# ultrasonic.net
KiCad netlist of a schematic drawn in EAGLE
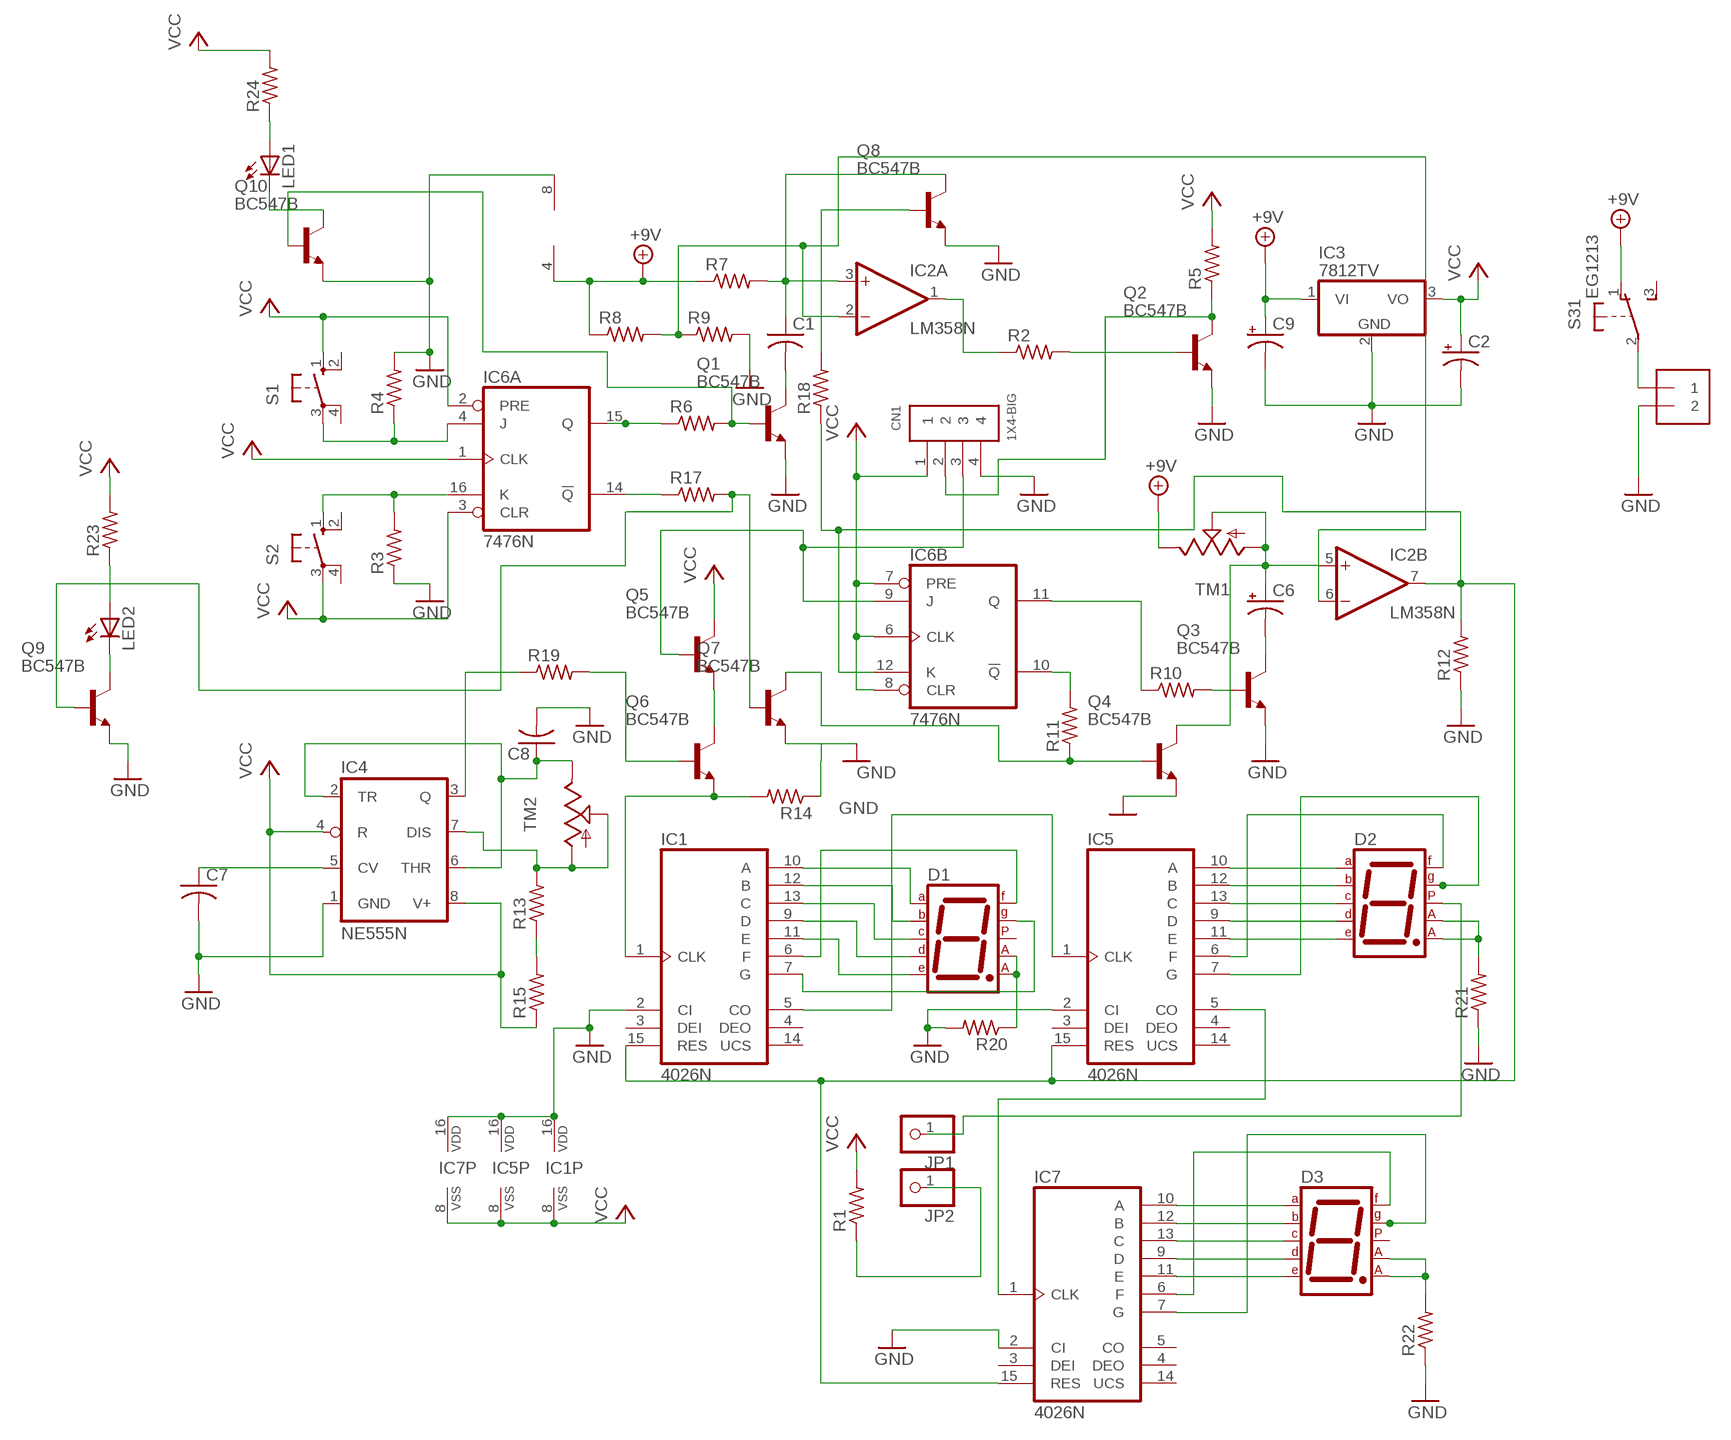
[diagram p0: schematic, sheet 1]

(export (version "E")
  (design (tool "Eeschema 10.0.6"))
  (components
    (comp (ref "C1")
      (value "C-US025-040X050")
      (footprint "eagle-import:C025-040X050")
      (libsource (lib "eagle-import") (part "C-US025-040X050"))
    )
    (comp (ref "C2")
      (value "CPOL-USE2-4")
      (footprint "eagle-import:E2-4")
      (libsource (lib "eagle-import") (part "CPOL-USE2-4"))
    )
    (comp (ref "C6")
      (value "CPOL-USE2.5-6")
      (footprint "eagle-import:E2,5-6")
      (libsource (lib "eagle-import") (part "CPOL-USE2.5-6"))
    )
    (comp (ref "C7")
      (value "C-US025-040X050")
      (footprint "eagle-import:C025-040X050")
      (libsource (lib "eagle-import") (part "C-US025-040X050"))
    )
    (comp (ref "C8")
      (value "C-US025-040X050")
      (footprint "eagle-import:C025-040X050")
      (libsource (lib "eagle-import") (part "C-US025-040X050"))
    )
    (comp (ref "C9")
      (value "CPOL-USE2.5-6")
      (footprint "eagle-import:E2,5-6")
      (libsource (lib "eagle-import") (part "CPOL-USE2.5-6"))
    )
    (comp (ref "CN1")
      (value "1X4-BIG")
      (footprint "eagle-import:1X04-BIG")
      (libsource (lib "eagle-import") (part "1X4-BIG"))
    )
    (comp (ref "D1")
      (value "7SEG-CA")
      (footprint "eagle-import:7SEG-13")
      (libsource (lib "eagle-import") (part "7SEG-CA"))
    )
    (comp (ref "D2")
      (value "7SEG-CA")
      (footprint "eagle-import:7SEG-13")
      (libsource (lib "eagle-import") (part "7SEG-CA"))
    )
    (comp (ref "D3")
      (value "7SEG-CA")
      (footprint "eagle-import:7SEG-13")
      (libsource (lib "eagle-import") (part "7SEG-CA"))
    )
    (comp (ref "IC1")
      (value "4026N")
      (footprint "eagle-import:DIL16")
      (libsource (lib "eagle-import") (part "4026N"))
    )
    (comp (ref "IC2")
      (value "LM358N")
      (footprint "eagle-import:DIL08")
      (libsource (lib "eagle-import") (part "LM358N"))
    )
    (comp (ref "IC3")
      (value "7812TV")
      (footprint "eagle-import:TO220V")
      (libsource (lib "eagle-import") (part "78TV12"))
    )
    (comp (ref "IC4")
      (value "NE555N")
      (footprint "eagle-import:DIL08-ROUND")
      (libsource (lib "eagle-import") (part "555NNE"))
    )
    (comp (ref "IC5")
      (value "4026N")
      (footprint "eagle-import:DIL16")
      (libsource (lib "eagle-import") (part "4026N"))
    )
    (comp (ref "IC6")
      (value "7476N")
      (footprint "eagle-import:DIL16")
      (libsource (lib "eagle-import") (part "7476N"))
    )
    (comp (ref "IC7")
      (value "4026N")
      (footprint "eagle-import:DIL16")
      (libsource (lib "eagle-import") (part "4026N"))
    )
    (comp (ref "J1")
      (value "1X2-3.5MM")
      (footprint "eagle-import:1X2-3.5MM")
      (libsource (lib "eagle-import") (part "1X2-3.5MM"))
    )
    (comp (ref "JP1")
      (value "PINHD-1X1")
      (footprint "eagle-import:1X01")
      (libsource (lib "eagle-import") (part "PINHD-1X1"))
    )
    (comp (ref "JP2")
      (value "PINHD-1X1")
      (footprint "eagle-import:1X01")
      (libsource (lib "eagle-import") (part "PINHD-1X1"))
    )
    (comp (ref "LED1")
      (value "LED5MM")
      (footprint "eagle-import:LED5MM")
      (libsource (lib "eagle-import") (part "LED5MM"))
    )
    (comp (ref "LED2")
      (value "LED5MM")
      (footprint "eagle-import:LED5MM")
      (libsource (lib "eagle-import") (part "LED5MM"))
    )
    (comp (ref "Q1")
      (value "BC547B")
      (footprint "eagle-import:TO92")
      (libsource (lib "eagle-import") (part "BC547B"))
    )
    (comp (ref "Q2")
      (value "BC547B")
      (footprint "eagle-import:TO92")
      (libsource (lib "eagle-import") (part "BC547B"))
    )
    (comp (ref "Q3")
      (value "BC547B")
      (footprint "eagle-import:TO92")
      (libsource (lib "eagle-import") (part "BC547B"))
    )
    (comp (ref "Q4")
      (value "BC547B")
      (footprint "eagle-import:TO92")
      (libsource (lib "eagle-import") (part "BC547B"))
    )
    (comp (ref "Q5")
      (value "BC547B")
      (footprint "eagle-import:TO92")
      (libsource (lib "eagle-import") (part "BC547B"))
    )
    (comp (ref "Q6")
      (value "BC547B")
      (footprint "eagle-import:TO92")
      (libsource (lib "eagle-import") (part "BC547B"))
    )
    (comp (ref "Q7")
      (value "BC547B")
      (footprint "eagle-import:TO92")
      (libsource (lib "eagle-import") (part "BC547B"))
    )
    (comp (ref "Q8")
      (value "BC547B")
      (footprint "eagle-import:TO92")
      (libsource (lib "eagle-import") (part "BC547B"))
    )
    (comp (ref "Q9")
      (value "BC547B")
      (footprint "eagle-import:TO92")
      (libsource (lib "eagle-import") (part "BC547B"))
    )
    (comp (ref "Q10")
      (value "BC547B")
      (footprint "eagle-import:TO92")
      (libsource (lib "eagle-import") (part "BC547B"))
    )
    (comp (ref "R1")
      (value "R-US_0204/7")
      (footprint "eagle-import:0204_7")
      (libsource (lib "eagle-import") (part "R-US_0204/7"))
    )
    (comp (ref "R2")
      (value "R-US_0204/7")
      (footprint "eagle-import:0204_7")
      (libsource (lib "eagle-import") (part "R-US_0204/7"))
    )
    (comp (ref "R3")
      (value "R-US_0204/7")
      (footprint "eagle-import:0204_7")
      (libsource (lib "eagle-import") (part "R-US_0204/7"))
    )
    (comp (ref "R4")
      (value "R-US_0204/7")
      (footprint "eagle-import:0204_7")
      (libsource (lib "eagle-import") (part "R-US_0204/7"))
    )
    (comp (ref "R5")
      (value "R-US_0204/7")
      (footprint "eagle-import:0204_7")
      (libsource (lib "eagle-import") (part "R-US_0204/7"))
    )
    (comp (ref "R6")
      (value "R-US_0204/7")
      (footprint "eagle-import:0204_7")
      (libsource (lib "eagle-import") (part "R-US_0204/7"))
    )
    (comp (ref "R7")
      (value "R-US_0204/7")
      (footprint "eagle-import:0204_7")
      (libsource (lib "eagle-import") (part "R-US_0204/7"))
    )
    (comp (ref "R8")
      (value "R-US_0204/7")
      (footprint "eagle-import:0204_7")
      (libsource (lib "eagle-import") (part "R-US_0204/7"))
    )
    (comp (ref "R9")
      (value "R-US_0204/7")
      (footprint "eagle-import:0204_7")
      (libsource (lib "eagle-import") (part "R-US_0204/7"))
    )
    (comp (ref "R10")
      (value "R-US_0204/7")
      (footprint "eagle-import:0204_7")
      (libsource (lib "eagle-import") (part "R-US_0204/7"))
    )
    (comp (ref "R11")
      (value "R-US_0204/7")
      (footprint "eagle-import:0204_7")
      (libsource (lib "eagle-import") (part "R-US_0204/7"))
    )
    (comp (ref "R12")
      (value "R-US_0204/7")
      (footprint "eagle-import:0204_7")
      (libsource (lib "eagle-import") (part "R-US_0204/7"))
    )
    (comp (ref "R13")
      (value "R-US_0204/7")
      (footprint "eagle-import:0204_7")
      (libsource (lib "eagle-import") (part "R-US_0204/7"))
    )
    (comp (ref "R14")
      (value "R-US_0204/7")
      (footprint "eagle-import:0204_7")
      (libsource (lib "eagle-import") (part "R-US_0204/7"))
    )
    (comp (ref "R15")
      (value "R-US_0204/7")
      (footprint "eagle-import:0204_7")
      (libsource (lib "eagle-import") (part "R-US_0204/7"))
    )
    (comp (ref "R17")
      (value "R-US_0204/7")
      (footprint "eagle-import:0204_7")
      (libsource (lib "eagle-import") (part "R-US_0204/7"))
    )
    (comp (ref "R18")
      (value "R-US_0204/7")
      (footprint "eagle-import:0204_7")
      (libsource (lib "eagle-import") (part "R-US_0204/7"))
    )
    (comp (ref "R19")
      (value "R-US_0204/7")
      (footprint "eagle-import:0204_7")
      (libsource (lib "eagle-import") (part "R-US_0204/7"))
    )
    (comp (ref "R20")
      (value "R-US_0204/7")
      (footprint "eagle-import:0204_7")
      (libsource (lib "eagle-import") (part "R-US_0204/7"))
    )
    (comp (ref "R21")
      (value "R-US_0204/7")
      (footprint "eagle-import:0204_7")
      (libsource (lib "eagle-import") (part "R-US_0204/7"))
    )
    (comp (ref "R22")
      (value "R-US_0204/7")
      (footprint "eagle-import:0204_7")
      (libsource (lib "eagle-import") (part "R-US_0204/7"))
    )
    (comp (ref "R23")
      (value "R-US_0204/7")
      (footprint "eagle-import:0204_7")
      (libsource (lib "eagle-import") (part "R-US_0204/7"))
    )
    (comp (ref "R24")
      (value "R-US_0204/7")
      (footprint "eagle-import:0204_7")
      (libsource (lib "eagle-import") (part "R-US_0204/7"))
    )
    (comp (ref "S1")
      (value "10-XX")
      (footprint "eagle-import:B3F-10XX")
      (fields (field (name "MPN") "B3F-1000"))
      (libsource (lib "eagle-import") (part "10-XX"))
    )
    (comp (ref "S2")
      (value "10-XX")
      (footprint "eagle-import:B3F-10XX")
      (fields (field (name "MPN") "B3F-1000"))
      (libsource (lib "eagle-import") (part "10-XX"))
    )
    (comp (ref "S3")
      (value "EG1213")
      (footprint "eagle-import:EG1213")
      (libsource (lib "eagle-import") (part "EG1213"))
    )
    (comp (ref "TM1")
      (value "TRIM")
      (footprint "eagle-import:6MM")
      (libsource (lib "eagle-import") (part "TRIM"))
    )
    (comp (ref "TM2")
      (value "TRIM")
      (footprint "eagle-import:6MM")
      (libsource (lib "eagle-import") (part "TRIM"))
    )
  )
  (nets
    (net (code "1") (name "+9V") (class "Default")
      (node (ref "C9") (pin "+") (pinfunction "+_+") (pintype "passive"))
      (node (ref "IC2") (pin "4") (pinfunction "V-_4") (pintype "power_in"))
      (node (ref "IC3") (pin "1") (pinfunction "VI_1") (pintype "input"))
      (node (ref "R7") (pin "1") (pinfunction "1_1") (pintype "passive"))
      (node (ref "R8") (pin "1") (pinfunction "1_1") (pintype "passive"))
      (node (ref "S3") (pin "1") (pinfunction "O_1") (pintype "passive"))
      (node (ref "TM1") (pin "E") (pinfunction "E_E") (pintype "passive"))
    )
    (net (code "2") (name "GND") (class "Default")
      (node (ref "C2") (pin "-") (pinfunction "-_-") (pintype "passive"))
      (node (ref "C7") (pin "2") (pinfunction "2_2") (pintype "passive"))
      (node (ref "C8") (pin "2") (pinfunction "2_2") (pintype "passive"))
      (node (ref "C9") (pin "-") (pinfunction "-_-") (pintype "passive"))
      (node (ref "CN1") (pin "4") (pinfunction "4_4") (pintype "bidirectional"))
      (node (ref "IC1") (pin "16") (pinfunction "VDD_16") (pintype "power_in"))
      (node (ref "IC1") (pin "2") (pinfunction "CI_2") (pintype "input"))
      (node (ref "IC2") (pin "8") (pinfunction "V+_8") (pintype "power_in"))
      (node (ref "IC3") (pin "2") (pinfunction "GND_2") (pintype "passive"))
      (node (ref "IC4") (pin "1") (pinfunction "GND_1") (pintype "power_in"))
      (node (ref "IC5") (pin "16") (pinfunction "VDD_16") (pintype "power_in"))
      (node (ref "IC5") (pin "2") (pinfunction "CI_2") (pintype "input"))
      (node (ref "IC7") (pin "16") (pinfunction "VDD_16") (pintype "power_in"))
      (node (ref "IC7") (pin "2") (pinfunction "CI_2") (pintype "input"))
      (node (ref "J1") (pin "2") (pinfunction "2_2") (pintype "passive"))
      (node (ref "Q1") (pin "1") (pinfunction "E_1") (pintype "passive"))
      (node (ref "Q10") (pin "1") (pinfunction "E_1") (pintype "passive"))
      (node (ref "Q2") (pin "1") (pinfunction "E_1") (pintype "passive"))
      (node (ref "Q3") (pin "1") (pinfunction "E_1") (pintype "passive"))
      (node (ref "Q4") (pin "1") (pinfunction "E_1") (pintype "passive"))
      (node (ref "Q7") (pin "1") (pinfunction "E_1") (pintype "passive"))
      (node (ref "Q8") (pin "1") (pinfunction "E_1") (pintype "passive"))
      (node (ref "Q9") (pin "1") (pinfunction "E_1") (pintype "passive"))
      (node (ref "R12") (pin "1") (pinfunction "1_1") (pintype "passive"))
      (node (ref "R14") (pin "1") (pinfunction "1_1") (pintype "passive"))
      (node (ref "R20") (pin "2") (pinfunction "2_2") (pintype "passive"))
      (node (ref "R21") (pin "1") (pinfunction "1_1") (pintype "passive"))
      (node (ref "R22") (pin "1") (pinfunction "1_1") (pintype "passive"))
      (node (ref "R3") (pin "1") (pinfunction "1_1") (pintype "passive"))
      (node (ref "R4") (pin "2") (pinfunction "2_2") (pintype "passive"))
      (node (ref "R9") (pin "2") (pinfunction "2_2") (pintype "passive"))
    )
    (net (code "3") (name "Net-(D1-A)") (class "Default")
      (node (ref "D1") (pin "7") (pinfunction "A_7") (pintype "passive"))
      (node (ref "IC1") (pin "10") (pinfunction "A_10") (pintype "output"))
    )
    (net (code "4") (name "Net-(D1-B)") (class "Default")
      (node (ref "D1") (pin "6") (pinfunction "B_6") (pintype "passive"))
      (node (ref "IC1") (pin "12") (pinfunction "B_12") (pintype "output"))
    )
    (net (code "5") (name "Net-(D1-C)") (class "Default")
      (node (ref "D1") (pin "4") (pinfunction "C_4") (pintype "passive"))
      (node (ref "IC1") (pin "13") (pinfunction "C_13") (pintype "output"))
    )
    (net (code "6") (name "Net-(D1-CA1)") (class "Default")
      (node (ref "D1") (pin "3") (pinfunction "CA1_3") (pintype "passive"))
      (node (ref "D1") (pin "8") (pinfunction "CA2_8") (pintype "passive"))
      (node (ref "R20") (pin "1") (pinfunction "1_1") (pintype "passive"))
    )
    (net (code "7") (name "Net-(D1-D)") (class "Default")
      (node (ref "D1") (pin "2") (pinfunction "D_2") (pintype "passive"))
      (node (ref "IC1") (pin "9") (pinfunction "D_9") (pintype "output"))
    )
    (net (code "8") (name "Net-(D1-E)") (class "Default")
      (node (ref "D1") (pin "1") (pinfunction "E_1") (pintype "passive"))
      (node (ref "IC1") (pin "11") (pinfunction "E_11") (pintype "output"))
    )
    (net (code "9") (name "Net-(D1-F)") (class "Default")
      (node (ref "D1") (pin "9") (pinfunction "F_9") (pintype "passive"))
      (node (ref "IC1") (pin "6") (pinfunction "F_6") (pintype "output"))
    )
    (net (code "10") (name "Net-(D1-G)") (class "Default")
      (node (ref "D1") (pin "10") (pinfunction "G_10") (pintype "passive"))
      (node (ref "IC1") (pin "7") (pinfunction "G_7") (pintype "output"))
    )
    (net (code "11") (name "Net-(D2-A)") (class "Default")
      (node (ref "D2") (pin "7") (pinfunction "A_7") (pintype "passive"))
      (node (ref "IC5") (pin "10") (pinfunction "A_10") (pintype "output"))
    )
    (net (code "12") (name "Net-(D2-B)") (class "Default")
      (node (ref "D2") (pin "6") (pinfunction "B_6") (pintype "passive"))
      (node (ref "IC5") (pin "12") (pinfunction "B_12") (pintype "output"))
    )
    (net (code "13") (name "Net-(D2-C)") (class "Default")
      (node (ref "D2") (pin "4") (pinfunction "C_4") (pintype "passive"))
      (node (ref "IC5") (pin "13") (pinfunction "C_13") (pintype "output"))
    )
    (net (code "14") (name "Net-(D2-CA1)") (class "Default")
      (node (ref "D2") (pin "3") (pinfunction "CA1_3") (pintype "passive"))
      (node (ref "D2") (pin "8") (pinfunction "CA2_8") (pintype "passive"))
      (node (ref "R21") (pin "2") (pinfunction "2_2") (pintype "passive"))
    )
    (net (code "15") (name "Net-(D2-D)") (class "Default")
      (node (ref "D2") (pin "2") (pinfunction "D_2") (pintype "passive"))
      (node (ref "IC5") (pin "9") (pinfunction "D_9") (pintype "output"))
    )
    (net (code "16") (name "Net-(D2-DP)") (class "Default")
      (node (ref "D2") (pin "5") (pinfunction "DP_5") (pintype "passive"))
      (node (ref "JP1") (pin "1") (pinfunction "1_1") (pintype "passive"))
    )
    (net (code "17") (name "Net-(D2-E)") (class "Default")
      (node (ref "D2") (pin "1") (pinfunction "E_1") (pintype "passive"))
      (node (ref "IC5") (pin "11") (pinfunction "E_11") (pintype "output"))
    )
    (net (code "18") (name "Net-(D2-F)") (class "Default")
      (node (ref "D2") (pin "9") (pinfunction "F_9") (pintype "passive"))
      (node (ref "IC5") (pin "6") (pinfunction "F_6") (pintype "output"))
    )
    (net (code "19") (name "Net-(D2-G)") (class "Default")
      (node (ref "D2") (pin "10") (pinfunction "G_10") (pintype "passive"))
      (node (ref "IC5") (pin "7") (pinfunction "G_7") (pintype "output"))
    )
    (net (code "20") (name "Net-(D3-A)") (class "Default")
      (node (ref "D3") (pin "7") (pinfunction "A_7") (pintype "passive"))
      (node (ref "IC7") (pin "10") (pinfunction "A_10") (pintype "output"))
    )
    (net (code "21") (name "Net-(D3-B)") (class "Default")
      (node (ref "D3") (pin "6") (pinfunction "B_6") (pintype "passive"))
      (node (ref "IC7") (pin "12") (pinfunction "B_12") (pintype "output"))
    )
    (net (code "22") (name "Net-(D3-C)") (class "Default")
      (node (ref "D3") (pin "4") (pinfunction "C_4") (pintype "passive"))
      (node (ref "IC7") (pin "13") (pinfunction "C_13") (pintype "output"))
    )
    (net (code "23") (name "Net-(D3-CA1)") (class "Default")
      (node (ref "D3") (pin "3") (pinfunction "CA1_3") (pintype "passive"))
      (node (ref "D3") (pin "8") (pinfunction "CA2_8") (pintype "passive"))
      (node (ref "R22") (pin "2") (pinfunction "2_2") (pintype "passive"))
    )
    (net (code "24") (name "Net-(D3-D)") (class "Default")
      (node (ref "D3") (pin "2") (pinfunction "D_2") (pintype "passive"))
      (node (ref "IC7") (pin "9") (pinfunction "D_9") (pintype "output"))
    )
    (net (code "25") (name "Net-(D3-E)") (class "Default")
      (node (ref "D3") (pin "1") (pinfunction "E_1") (pintype "passive"))
      (node (ref "IC7") (pin "11") (pinfunction "E_11") (pintype "output"))
    )
    (net (code "26") (name "Net-(D3-F)") (class "Default")
      (node (ref "D3") (pin "9") (pinfunction "F_9") (pintype "passive"))
      (node (ref "IC7") (pin "6") (pinfunction "F_6") (pintype "output"))
    )
    (net (code "27") (name "Net-(D3-G)") (class "Default")
      (node (ref "D3") (pin "10") (pinfunction "G_10") (pintype "passive"))
      (node (ref "IC7") (pin "7") (pinfunction "G_7") (pintype "output"))
    )
    (net (code "28") (name "Net-(IC1A-CLK)") (class "Default")
      (node (ref "IC1") (pin "1") (pinfunction "CLK_1") (pintype "input"))
      (node (ref "Q6") (pin "1") (pinfunction "E_1") (pintype "passive"))
      (node (ref "R14") (pin "2") (pinfunction "2_2") (pintype "passive"))
    )
    (net (code "29") (name "Net-(IC1A-CO)") (class "Default")
      (node (ref "IC1") (pin "5") (pinfunction "CO_5") (pintype "output"))
      (node (ref "IC5") (pin "1") (pinfunction "CLK_1") (pintype "input"))
    )
    (net (code "30") (name "Net-(IC1A-RES)") (class "Default")
      (node (ref "IC1") (pin "15") (pinfunction "RES_15") (pintype "input"))
      (node (ref "IC2") (pin "7") (pinfunction "OUT_7") (pintype "output"))
      (node (ref "IC5") (pin "15") (pinfunction "RES_15") (pintype "input"))
      (node (ref "IC6") (pin "12") (pinfunction "K_12") (pintype "input"))
      (node (ref "IC7") (pin "15") (pinfunction "RES_15") (pintype "input"))
      (node (ref "R12") (pin "2") (pinfunction "2_2") (pintype "passive"))
      (node (ref "R18") (pin "1") (pinfunction "1_1") (pintype "passive"))
    )
    (net (code "31") (name "Net-(IC2A-+IN)") (class "Default")
      (node (ref "C1") (pin "1") (pinfunction "1_1") (pintype "passive"))
      (node (ref "IC2") (pin "3") (pinfunction "+IN_3") (pintype "input"))
      (node (ref "Q8") (pin "3") (pinfunction "C_3") (pintype "passive"))
      (node (ref "R7") (pin "2") (pinfunction "2_2") (pintype "passive"))
    )
    (net (code "32") (name "Net-(IC2A--IN)") (class "Default")
      (node (ref "IC2") (pin "2") (pinfunction "-IN_2") (pintype "input"))
      (node (ref "IC2") (pin "6") (pinfunction "-IN_6") (pintype "input"))
      (node (ref "R8") (pin "2") (pinfunction "2_2") (pintype "passive"))
      (node (ref "R9") (pin "1") (pinfunction "1_1") (pintype "passive"))
    )
    (net (code "33") (name "Net-(IC2A-OUT)") (class "Default")
      (node (ref "IC2") (pin "1") (pinfunction "OUT_1") (pintype "output"))
      (node (ref "R2") (pin "1") (pinfunction "1_1") (pintype "passive"))
    )
    (net (code "34") (name "Net-(IC2B-+IN)") (class "Default")
      (node (ref "C6") (pin "+") (pinfunction "+_+") (pintype "passive"))
      (node (ref "IC2") (pin "5") (pinfunction "+IN_5") (pintype "input"))
      (node (ref "Q4") (pin "3") (pinfunction "C_3") (pintype "passive"))
      (node (ref "TM1") (pin "A") (pinfunction "A_A") (pintype "passive"))
      (node (ref "TM1") (pin "S") (pinfunction "S_S") (pintype "passive"))
    )
    (net (code "35") (name "Net-(IC4-CV)") (class "Default")
      (node (ref "C7") (pin "1") (pinfunction "1_1") (pintype "passive"))
      (node (ref "IC4") (pin "5") (pinfunction "CV_5") (pintype "input"))
    )
    (net (code "36") (name "Net-(IC4-DIS)") (class "Default")
      (node (ref "IC4") (pin "7") (pinfunction "DIS_7") (pintype "input"))
      (node (ref "R13") (pin "2") (pinfunction "2_2") (pintype "passive"))
      (node (ref "TM2") (pin "A") (pinfunction "A_A") (pintype "passive"))
      (node (ref "TM2") (pin "S") (pinfunction "S_S") (pintype "passive"))
    )
    (net (code "37") (name "Net-(IC4-Q)") (class "Default")
      (node (ref "IC4") (pin "3") (pinfunction "Q_3") (pintype "output"))
      (node (ref "R19") (pin "1") (pinfunction "1_1") (pintype "passive"))
    )
    (net (code "38") (name "Net-(IC4-THR)") (class "Default")
      (node (ref "C8") (pin "1") (pinfunction "1_1") (pintype "passive"))
      (node (ref "IC4") (pin "2") (pinfunction "TR_2") (pintype "input"))
      (node (ref "IC4") (pin "6") (pinfunction "THR_6") (pintype "input"))
      (node (ref "TM2") (pin "E") (pinfunction "E_E") (pintype "passive"))
    )
    (net (code "39") (name "Net-(IC5A-CO)") (class "Default")
      (node (ref "IC5") (pin "5") (pinfunction "CO_5") (pintype "output"))
      (node (ref "IC7") (pin "1") (pinfunction "CLK_1") (pintype "input"))
    )
    (net (code "40") (name "Net-(IC6A-J)") (class "Default")
      (node (ref "IC6") (pin "4") (pinfunction "J_4") (pintype "input"))
      (node (ref "R4") (pin "1") (pinfunction "1_1") (pintype "passive"))
      (node (ref "S1") (pin "3") (pinfunction "P_3") (pintype "passive"))
    )
    (net (code "41") (name "Net-(IC6A-K)") (class "Default")
      (node (ref "IC6") (pin "16") (pinfunction "K_16") (pintype "input"))
      (node (ref "R3") (pin "2") (pinfunction "2_2") (pintype "passive"))
      (node (ref "S2") (pin "1") (pinfunction "S_1") (pintype "passive"))
    )
    (net (code "42") (name "Net-(IC6A-Q)") (class "Default")
      (node (ref "IC6") (pin "15") (pinfunction "Q_15") (pintype "output"))
      (node (ref "R6") (pin "1") (pinfunction "1_1") (pintype "passive"))
    )
    (net (code "43") (name "Net-(IC6A-~{Q})") (class "Default")
      (node (ref "IC6") (pin "14") (pinfunction "~{Q}_14") (pintype "output"))
      (node (ref "R17") (pin "1") (pinfunction "1_1") (pintype "passive"))
    )
    (net (code "44") (name "Net-(IC6B-J)") (class "Default")
      (node (ref "CN1") (pin "3") (pinfunction "3_3") (pintype "bidirectional"))
      (node (ref "IC6") (pin "9") (pinfunction "J_9") (pintype "input"))
      (node (ref "Q5") (pin "2") (pinfunction "B_2") (pintype "passive"))
    )
    (net (code "45") (name "Net-(IC6B-Q)") (class "Default")
      (node (ref "IC6") (pin "11") (pinfunction "Q_11") (pintype "output"))
      (node (ref "R10") (pin "1") (pinfunction "1_1") (pintype "passive"))
    )
    (net (code "46") (name "Net-(IC6B-~{Q})") (class "Default")
      (node (ref "IC6") (pin "10") (pinfunction "~{Q}_10") (pintype "output"))
      (node (ref "R11") (pin "2") (pinfunction "2_2") (pintype "passive"))
    )
    (net (code "47") (name "Net-(JP2-Pad1)") (class "Default")
      (node (ref "JP2") (pin "1") (pinfunction "1_1") (pintype "passive"))
      (node (ref "R1") (pin "1") (pinfunction "1_1") (pintype "passive"))
    )
    (net (code "48") (name "Net-(LED1-C)") (class "Default")
      (node (ref "LED1") (pin "K") (pinfunction "C_K") (pintype "passive"))
      (node (ref "Q10") (pin "3") (pinfunction "C_3") (pintype "passive"))
    )
    (net (code "49") (name "Net-(LED1-PadA)") (class "Default")
      (node (ref "LED1") (pin "A") (pinfunction "A_A") (pintype "passive"))
      (node (ref "R24") (pin "1") (pinfunction "1_1") (pintype "passive"))
    )
    (net (code "50") (name "Net-(LED2-C)") (class "Default")
      (node (ref "LED2") (pin "K") (pinfunction "C_K") (pintype "passive"))
      (node (ref "Q9") (pin "3") (pinfunction "C_3") (pintype "passive"))
    )
    (net (code "51") (name "Net-(LED2-PadA)") (class "Default")
      (node (ref "LED2") (pin "A") (pinfunction "A_A") (pintype "passive"))
      (node (ref "R23") (pin "1") (pinfunction "1_1") (pintype "passive"))
    )
    (net (code "52") (name "Net-(Q1-B)") (class "Default")
      (node (ref "Q1") (pin "2") (pinfunction "B_2") (pintype "passive"))
      (node (ref "Q10") (pin "2") (pinfunction "B_2") (pintype "passive"))
      (node (ref "R6") (pin "2") (pinfunction "2_2") (pintype "passive"))
    )
    (net (code "53") (name "Net-(Q1-C)") (class "Default")
      (node (ref "C1") (pin "2") (pinfunction "2_2") (pintype "passive"))
      (node (ref "Q1") (pin "3") (pinfunction "C_3") (pintype "passive"))
    )
    (net (code "54") (name "Net-(Q2-B)") (class "Default")
      (node (ref "Q2") (pin "2") (pinfunction "B_2") (pintype "passive"))
      (node (ref "R2") (pin "2") (pinfunction "2_2") (pintype "passive"))
    )
    (net (code "55") (name "Net-(Q2-C)") (class "Default")
      (node (ref "CN1") (pin "2") (pinfunction "2_2") (pintype "bidirectional"))
      (node (ref "Q2") (pin "3") (pinfunction "C_3") (pintype "passive"))
      (node (ref "R5") (pin "1") (pinfunction "1_1") (pintype "passive"))
    )
    (net (code "56") (name "Net-(Q3-B)") (class "Default")
      (node (ref "Q3") (pin "2") (pinfunction "B_2") (pintype "passive"))
      (node (ref "R10") (pin "2") (pinfunction "2_2") (pintype "passive"))
    )
    (net (code "57") (name "Net-(Q3-C)") (class "Default")
      (node (ref "C6") (pin "-") (pinfunction "-_-") (pintype "passive"))
      (node (ref "Q3") (pin "3") (pinfunction "C_3") (pintype "passive"))
    )
    (net (code "58") (name "Net-(Q4-B)") (class "Default")
      (node (ref "Q4") (pin "2") (pinfunction "B_2") (pintype "passive"))
      (node (ref "Q7") (pin "3") (pinfunction "C_3") (pintype "passive"))
      (node (ref "R11") (pin "1") (pinfunction "1_1") (pintype "passive"))
    )
    (net (code "59") (name "Net-(Q5-E)") (class "Default")
      (node (ref "Q5") (pin "1") (pinfunction "E_1") (pintype "passive"))
      (node (ref "Q6") (pin "3") (pinfunction "C_3") (pintype "passive"))
    )
    (net (code "60") (name "Net-(Q6-B)") (class "Default")
      (node (ref "Q6") (pin "2") (pinfunction "B_2") (pintype "passive"))
      (node (ref "R19") (pin "2") (pinfunction "2_2") (pintype "passive"))
    )
    (net (code "61") (name "Net-(Q7-B)") (class "Default")
      (node (ref "Q7") (pin "2") (pinfunction "B_2") (pintype "passive"))
      (node (ref "Q9") (pin "2") (pinfunction "B_2") (pintype "passive"))
      (node (ref "R17") (pin "2") (pinfunction "2_2") (pintype "passive"))
    )
    (net (code "62") (name "Net-(Q8-B)") (class "Default")
      (node (ref "Q8") (pin "2") (pinfunction "B_2") (pintype "passive"))
      (node (ref "R18") (pin "2") (pinfunction "2_2") (pintype "passive"))
    )
    (net (code "63") (name "Net-(R13-Pad1)") (class "Default")
      (node (ref "R13") (pin "1") (pinfunction "1_1") (pintype "passive"))
      (node (ref "R15") (pin "2") (pinfunction "2_2") (pintype "passive"))
    )
    (net (code "64") (name "Net-(S3A-P)") (class "Default")
      (node (ref "J1") (pin "1") (pinfunction "1_1") (pintype "passive"))
      (node (ref "S3") (pin "2") (pinfunction "P_2") (pintype "passive"))
    )
    (net (code "65") (name "VCC") (class "Default")
      (node (ref "C2") (pin "+") (pinfunction "+_+") (pintype "passive"))
      (node (ref "CN1") (pin "1") (pinfunction "1_1") (pintype "bidirectional"))
      (node (ref "IC1") (pin "8") (pinfunction "VSS_8") (pintype "power_in"))
      (node (ref "IC3") (pin "3") (pinfunction "VO_3") (pintype "passive"))
      (node (ref "IC4") (pin "4") (pinfunction "R_4") (pintype "input"))
      (node (ref "IC4") (pin "8") (pinfunction "V+_8") (pintype "power_in"))
      (node (ref "IC5") (pin "8") (pinfunction "VSS_8") (pintype "power_in"))
      (node (ref "IC6") (pin "1") (pinfunction "CLK_1") (pintype "input"))
      (node (ref "IC6") (pin "2") (pinfunction "PRE_2") (pintype "input"))
      (node (ref "IC6") (pin "3") (pinfunction "CLR_3") (pintype "input"))
      (node (ref "IC6") (pin "6") (pinfunction "CLK_6") (pintype "input"))
      (node (ref "IC6") (pin "7") (pinfunction "PRE_7") (pintype "input"))
      (node (ref "IC6") (pin "8") (pinfunction "CLR_8") (pintype "input"))
      (node (ref "IC7") (pin "8") (pinfunction "VSS_8") (pintype "power_in"))
      (node (ref "Q5") (pin "3") (pinfunction "C_3") (pintype "passive"))
      (node (ref "R1") (pin "2") (pinfunction "2_2") (pintype "passive"))
      (node (ref "R15") (pin "1") (pinfunction "1_1") (pintype "passive"))
      (node (ref "R23") (pin "2") (pinfunction "2_2") (pintype "passive"))
      (node (ref "R24") (pin "2") (pinfunction "2_2") (pintype "passive"))
      (node (ref "R5") (pin "2") (pinfunction "2_2") (pintype "passive"))
      (node (ref "S1") (pin "1") (pinfunction "S_1") (pintype "passive"))
      (node (ref "S2") (pin "3") (pinfunction "P_3") (pintype "passive"))
    )
    (net (code "66") (name "unconnected-(D1-DP-Pad5)") (class "Default")
      (node (ref "D1") (pin "5") (pinfunction "DP_5") (pintype "passive"))
    )
    (net (code "67") (name "unconnected-(D3-DP-Pad5)") (class "Default")
      (node (ref "D3") (pin "5") (pinfunction "DP_5") (pintype "passive"))
    )
    (net (code "68") (name "unconnected-(IC1A-DEI-Pad3)") (class "Default")
      (node (ref "IC1") (pin "3") (pinfunction "DEI_3") (pintype "input"))
    )
    (net (code "69") (name "unconnected-(IC1A-DEO-Pad4)") (class "Default")
      (node (ref "IC1") (pin "4") (pinfunction "DEO_4") (pintype "output"))
    )
    (net (code "70") (name "unconnected-(IC1A-UCS-Pad14)") (class "Default")
      (node (ref "IC1") (pin "14") (pinfunction "UCS_14") (pintype "output"))
    )
    (net (code "71") (name "unconnected-(IC5A-DEI-Pad3)") (class "Default")
      (node (ref "IC5") (pin "3") (pinfunction "DEI_3") (pintype "input"))
    )
    (net (code "72") (name "unconnected-(IC5A-DEO-Pad4)") (class "Default")
      (node (ref "IC5") (pin "4") (pinfunction "DEO_4") (pintype "output"))
    )
    (net (code "73") (name "unconnected-(IC5A-UCS-Pad14)") (class "Default")
      (node (ref "IC5") (pin "14") (pinfunction "UCS_14") (pintype "output"))
    )
    (net (code "74") (name "unconnected-(IC7A-CO-Pad5)") (class "Default")
      (node (ref "IC7") (pin "5") (pinfunction "CO_5") (pintype "output"))
    )
    (net (code "75") (name "unconnected-(IC7A-DEI-Pad3)") (class "Default")
      (node (ref "IC7") (pin "3") (pinfunction "DEI_3") (pintype "input"))
    )
    (net (code "76") (name "unconnected-(IC7A-DEO-Pad4)") (class "Default")
      (node (ref "IC7") (pin "4") (pinfunction "DEO_4") (pintype "output"))
    )
    (net (code "77") (name "unconnected-(IC7A-UCS-Pad14)") (class "Default")
      (node (ref "IC7") (pin "14") (pinfunction "UCS_14") (pintype "output"))
    )
    (net (code "78") (name "unconnected-(S1-P1-Pad4)") (class "Default")
      (node (ref "S1") (pin "4") (pinfunction "P1_4") (pintype "passive"))
    )
    (net (code "79") (name "unconnected-(S1-S1-Pad2)") (class "Default")
      (node (ref "S1") (pin "2") (pinfunction "S1_2") (pintype "passive"))
    )
    (net (code "80") (name "unconnected-(S2-P1-Pad4)") (class "Default")
      (node (ref "S2") (pin "4") (pinfunction "P1_4") (pintype "passive"))
    )
    (net (code "81") (name "unconnected-(S2-S1-Pad2)") (class "Default")
      (node (ref "S2") (pin "2") (pinfunction "S1_2") (pintype "passive"))
    )
    (net (code "82") (name "unconnected-(S3A-S-Pad3)") (class "Default")
      (node (ref "S3") (pin "3") (pinfunction "S_3") (pintype "passive"))
    )
  )
)
